# air_cylinder_control.net
KiCad netlist of a schematic drawn in Altium Designer
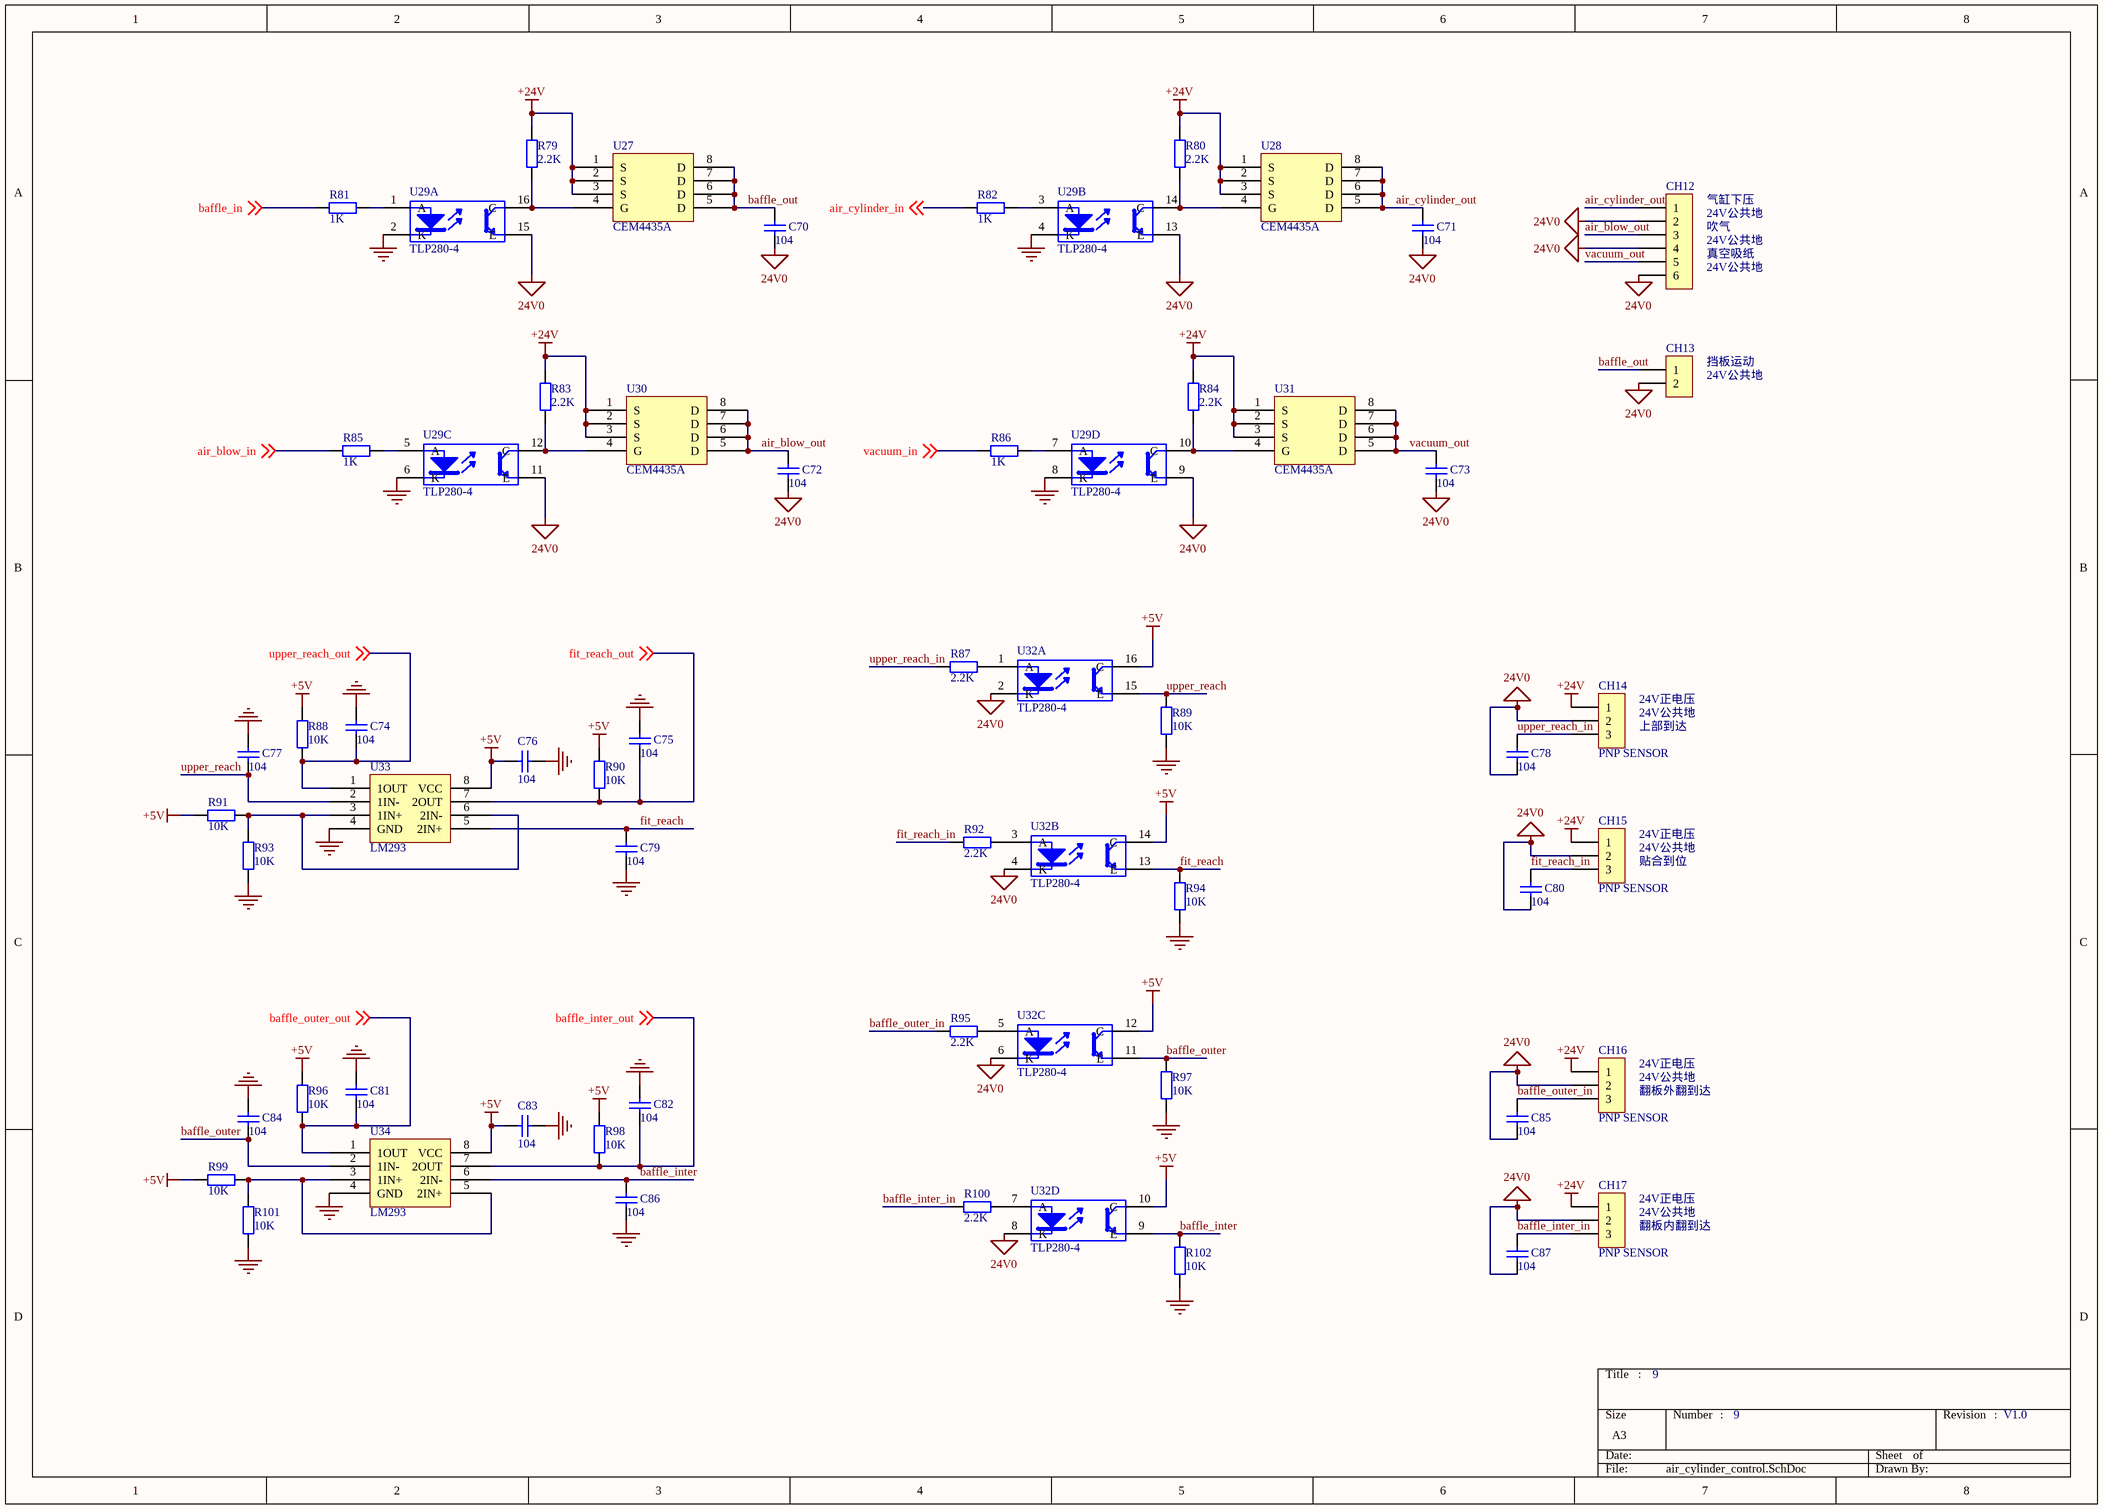
[diagram p0: air_cylinder_control.SchDoc]

(export (version "E")
  (design (tool "Eeschema 10.0.6"))
  (components
    (comp (ref "C70")
      (value "104")
      (footprint "0805")
      (description "Capacitor")
      (fields (field (name "Comment") "Cap") (field (name "PUBLISHER") "Altium Limited"))
      (libsource (lib "Miscellaneous Devices") (part "Cap"))
    )
    (comp (ref "C71")
      (value "104")
      (footprint "0805")
      (description "Capacitor")
      (fields (field (name "Comment") "Cap") (field (name "PUBLISHER") "Altium Limited"))
      (libsource (lib "Miscellaneous Devices") (part "Cap"))
    )
    (comp (ref "C72")
      (value "104")
      (footprint "0805")
      (description "Capacitor")
      (fields (field (name "Comment") "Cap") (field (name "PUBLISHER") "Altium Limited"))
      (libsource (lib "Miscellaneous Devices") (part "Cap"))
    )
    (comp (ref "C73")
      (value "104")
      (footprint "0805")
      (description "Capacitor")
      (fields (field (name "Comment") "Cap") (field (name "PUBLISHER") "Altium Limited"))
      (libsource (lib "Miscellaneous Devices") (part "Cap"))
    )
    (comp (ref "C74")
      (value "104")
      (footprint "0805")
      (description "Capacitor")
      (fields (field (name "Comment") "Cap") (field (name "PUBLISHER") "Altium Limited"))
      (libsource (lib "Miscellaneous Devices") (part "Cap"))
    )
    (comp (ref "C75")
      (value "104")
      (footprint "0805")
      (description "Capacitor")
      (fields (field (name "Comment") "Cap") (field (name "PUBLISHER") "Altium Limited"))
      (libsource (lib "Miscellaneous Devices") (part "Cap"))
    )
    (comp (ref "C76")
      (value "104")
      (footprint "0805")
      (description "Capacitor")
      (fields (field (name "Comment") "Cap") (field (name "PUBLISHER") "Altium Limited"))
      (libsource (lib "Miscellaneous Devices") (part "Cap"))
    )
    (comp (ref "C77")
      (value "104")
      (footprint "0805")
      (description "Capacitor")
      (fields (field (name "Comment") "Cap") (field (name "PUBLISHER") "Altium Limited"))
      (libsource (lib "Miscellaneous Devices") (part "Cap"))
    )
    (comp (ref "C78")
      (value "104")
      (footprint "0805")
      (description "Capacitor")
      (fields (field (name "Comment") "Cap") (field (name "PUBLISHER") "Altium Limited"))
      (libsource (lib "Miscellaneous Devices") (part "Cap"))
    )
    (comp (ref "C79")
      (value "104")
      (footprint "0805")
      (description "Capacitor")
      (fields (field (name "Comment") "Cap") (field (name "PUBLISHER") "Altium Limited"))
      (libsource (lib "Miscellaneous Devices") (part "Cap"))
    )
    (comp (ref "C80")
      (value "104")
      (footprint "0805")
      (description "Capacitor")
      (fields (field (name "Comment") "Cap") (field (name "PUBLISHER") "Altium Limited"))
      (libsource (lib "Miscellaneous Devices") (part "Cap"))
    )
    (comp (ref "C81")
      (value "104")
      (footprint "0805")
      (description "Capacitor")
      (fields (field (name "Comment") "Cap") (field (name "PUBLISHER") "Altium Limited"))
      (libsource (lib "Miscellaneous Devices") (part "Cap"))
    )
    (comp (ref "C82")
      (value "104")
      (footprint "0805")
      (description "Capacitor")
      (fields (field (name "Comment") "Cap") (field (name "PUBLISHER") "Altium Limited"))
      (libsource (lib "Miscellaneous Devices") (part "Cap"))
    )
    (comp (ref "C83")
      (value "104")
      (footprint "0805")
      (description "Capacitor")
      (fields (field (name "Comment") "Cap") (field (name "PUBLISHER") "Altium Limited"))
      (libsource (lib "Miscellaneous Devices") (part "Cap"))
    )
    (comp (ref "C84")
      (value "104")
      (footprint "0805")
      (description "Capacitor")
      (fields (field (name "Comment") "Cap") (field (name "PUBLISHER") "Altium Limited"))
      (libsource (lib "Miscellaneous Devices") (part "Cap"))
    )
    (comp (ref "C85")
      (value "104")
      (footprint "0805")
      (description "Capacitor")
      (fields (field (name "Comment") "Cap") (field (name "PUBLISHER") "Altium Limited"))
      (libsource (lib "Miscellaneous Devices") (part "Cap"))
    )
    (comp (ref "C86")
      (value "104")
      (footprint "0805")
      (description "Capacitor")
      (fields (field (name "Comment") "Cap") (field (name "PUBLISHER") "Altium Limited"))
      (libsource (lib "Miscellaneous Devices") (part "Cap"))
    )
    (comp (ref "C87")
      (value "104")
      (footprint "0805")
      (description "Capacitor")
      (fields (field (name "Comment") "Cap") (field (name "PUBLISHER") "Altium Limited"))
      (libsource (lib "Miscellaneous Devices") (part "Cap"))
    )
    (comp (ref "CH12")
      (value "HEADER1X6")
      (footprint "CH3.96-6PIN")
      (libsource (lib "myIntegrated_Library1") (part "HEADER1X6"))
    )
    (comp (ref "CH13")
      (value "HEADER1X2")
      (footprint "CH3.96-2PIN")
      (libsource (lib "myIntegrated_Library1") (part "HEADER1X2"))
    )
    (comp (ref "CH14")
      (value "HEADER1X3")
      (footprint "CH3.96-3PIN")
      (fields (field (name "ALTIUM_UNNAMED_1") "PNP SENSOR"))
      (libsource (lib "myIntegrated_Library1") (part "HEADER1X3"))
    )
    (comp (ref "CH15")
      (value "HEADER1X3")
      (footprint "CH3.96-3PIN")
      (fields (field (name "ALTIUM_UNNAMED_1") "PNP SENSOR"))
      (libsource (lib "myIntegrated_Library1") (part "HEADER1X3"))
    )
    (comp (ref "CH16")
      (value "HEADER1X3")
      (footprint "CH3.96-3PIN")
      (fields (field (name "ALTIUM_UNNAMED_1") "PNP SENSOR"))
      (libsource (lib "myIntegrated_Library1") (part "HEADER1X3"))
    )
    (comp (ref "CH17")
      (value "HEADER1X3")
      (footprint "CH3.96-3PIN")
      (fields (field (name "ALTIUM_UNNAMED_1") "PNP SENSOR"))
      (libsource (lib "myIntegrated_Library1") (part "HEADER1X3"))
    )
    (comp (ref "R79")
      (value "2.2K")
      (footprint "0805")
      (description "Resistor")
      (fields (field (name "Comment") "Res2") (field (name "PUBLISHER") "Altium Limited"))
      (libsource (lib "") (part "Res2_2"))
    )
    (comp (ref "R80")
      (value "2.2K")
      (footprint "0805")
      (description "Resistor")
      (fields (field (name "Comment") "Res2") (field (name "PUBLISHER") "Altium Limited"))
      (libsource (lib "") (part "Res2_2"))
    )
    (comp (ref "R81")
      (value "1K")
      (footprint "0805")
      (description "Resistor")
      (fields (field (name "Comment") "Res2") (field (name "PUBLISHER") "Altium Limited"))
      (libsource (lib "Miscellaneous Devices") (part "Res2"))
    )
    (comp (ref "R82")
      (value "1K")
      (footprint "0805")
      (description "Resistor")
      (fields (field (name "Comment") "Res2") (field (name "PUBLISHER") "Altium Limited"))
      (libsource (lib "Miscellaneous Devices") (part "Res2"))
    )
    (comp (ref "R83")
      (value "2.2K")
      (footprint "0805")
      (description "Resistor")
      (fields (field (name "Comment") "Res2") (field (name "PUBLISHER") "Altium Limited"))
      (libsource (lib "") (part "Res2_2"))
    )
    (comp (ref "R84")
      (value "2.2K")
      (footprint "0805")
      (description "Resistor")
      (fields (field (name "Comment") "Res2") (field (name "PUBLISHER") "Altium Limited"))
      (libsource (lib "") (part "Res2_2"))
    )
    (comp (ref "R85")
      (value "1K")
      (footprint "0805")
      (description "Resistor")
      (fields (field (name "Comment") "Res2") (field (name "PUBLISHER") "Altium Limited"))
      (libsource (lib "Miscellaneous Devices") (part "Res2"))
    )
    (comp (ref "R86")
      (value "1K")
      (footprint "0805")
      (description "Resistor")
      (fields (field (name "Comment") "Res2") (field (name "PUBLISHER") "Altium Limited"))
      (libsource (lib "Miscellaneous Devices") (part "Res2"))
    )
    (comp (ref "R87")
      (value "2.2K")
      (footprint "0805")
      (description "Resistor")
      (fields (field (name "Comment") "Res2") (field (name "PUBLISHER") "Altium Limited"))
      (libsource (lib "Miscellaneous Devices") (part "Res2"))
    )
    (comp (ref "R88")
      (value "10K")
      (footprint "0805")
      (description "Resistor")
      (fields (field (name "Comment") "Res2") (field (name "PUBLISHER") "Altium Limited"))
      (libsource (lib "") (part "Res2_1"))
    )
    (comp (ref "R89")
      (value "10K")
      (footprint "0805")
      (description "Resistor")
      (fields (field (name "Comment") "Res2") (field (name "PUBLISHER") "Altium Limited"))
      (libsource (lib "") (part "Res2_1"))
    )
    (comp (ref "R90")
      (value "10K")
      (footprint "0805")
      (description "Resistor")
      (fields (field (name "Comment") "Res2") (field (name "PUBLISHER") "Altium Limited"))
      (libsource (lib "") (part "Res2_1"))
    )
    (comp (ref "R91")
      (value "10K")
      (footprint "0805")
      (description "Resistor")
      (fields (field (name "Comment") "Res2") (field (name "PUBLISHER") "Altium Limited"))
      (libsource (lib "") (part "Res2_3"))
    )
    (comp (ref "R92")
      (value "2.2K")
      (footprint "0805")
      (description "Resistor")
      (fields (field (name "Comment") "Res2") (field (name "PUBLISHER") "Altium Limited"))
      (libsource (lib "Miscellaneous Devices") (part "Res2"))
    )
    (comp (ref "R93")
      (value "10K")
      (footprint "0805")
      (description "Resistor")
      (fields (field (name "Comment") "Res2") (field (name "PUBLISHER") "Altium Limited"))
      (libsource (lib "") (part "Res2_1"))
    )
    (comp (ref "R94")
      (value "10K")
      (footprint "0805")
      (description "Resistor")
      (fields (field (name "Comment") "Res2") (field (name "PUBLISHER") "Altium Limited"))
      (libsource (lib "") (part "Res2_1"))
    )
    (comp (ref "R95")
      (value "2.2K")
      (footprint "0805")
      (description "Resistor")
      (fields (field (name "Comment") "Res2") (field (name "PUBLISHER") "Altium Limited"))
      (libsource (lib "Miscellaneous Devices") (part "Res2"))
    )
    (comp (ref "R96")
      (value "10K")
      (footprint "0805")
      (description "Resistor")
      (fields (field (name "Comment") "Res2") (field (name "PUBLISHER") "Altium Limited"))
      (libsource (lib "") (part "Res2_1"))
    )
    (comp (ref "R97")
      (value "10K")
      (footprint "0805")
      (description "Resistor")
      (fields (field (name "Comment") "Res2") (field (name "PUBLISHER") "Altium Limited"))
      (libsource (lib "") (part "Res2_1"))
    )
    (comp (ref "R98")
      (value "10K")
      (footprint "0805")
      (description "Resistor")
      (fields (field (name "Comment") "Res2") (field (name "PUBLISHER") "Altium Limited"))
      (libsource (lib "") (part "Res2_1"))
    )
    (comp (ref "R99")
      (value "10K")
      (footprint "0805")
      (description "Resistor")
      (fields (field (name "Comment") "Res2") (field (name "PUBLISHER") "Altium Limited"))
      (libsource (lib "") (part "Res2_3"))
    )
    (comp (ref "R100")
      (value "2.2K")
      (footprint "0805")
      (description "Resistor")
      (fields (field (name "Comment") "Res2") (field (name "PUBLISHER") "Altium Limited"))
      (libsource (lib "Miscellaneous Devices") (part "Res2"))
    )
    (comp (ref "R101")
      (value "10K")
      (footprint "0805")
      (description "Resistor")
      (fields (field (name "Comment") "Res2") (field (name "PUBLISHER") "Altium Limited"))
      (libsource (lib "") (part "Res2_1"))
    )
    (comp (ref "R102")
      (value "10K")
      (footprint "0805")
      (description "Resistor")
      (fields (field (name "Comment") "Res2") (field (name "PUBLISHER") "Altium Limited"))
      (libsource (lib "") (part "Res2_1"))
    )
    (comp (ref "U27")
      (value "CEM4435A")
      (footprint "SOP8-OP27")
      (libsource (lib "myIntegrated_Library1") (part "CEM4435A"))
    )
    (comp (ref "U28")
      (value "CEM4435A")
      (footprint "SOP8-OP27")
      (libsource (lib "myIntegrated_Library1") (part "CEM4435A"))
    )
    (comp (ref "U29") (value "TLP280-4") (footprint "SO16") (libsource (lib "WH V20") (part "TLP521-4")))
    (comp (ref "U30")
      (value "CEM4435A")
      (footprint "SOP8-OP27")
      (libsource (lib "myIntegrated_Library1") (part "CEM4435A"))
    )
    (comp (ref "U31")
      (value "CEM4435A")
      (footprint "SOP8-OP27")
      (libsource (lib "myIntegrated_Library1") (part "CEM4435A"))
    )
    (comp (ref "U32") (value "TLP280-4") (footprint "SO16") (libsource (lib "WH V20") (part "TLP521-4")))
    (comp (ref "U33")
      (value "LM293")
      (footprint "SOP8-OP27")
      (libsource (lib "myIntegrated_Library1") (part "LM293"))
    )
    (comp (ref "U34")
      (value "LM293")
      (footprint "SOP8-OP27")
      (libsource (lib "myIntegrated_Library1") (part "LM293"))
    )
  )
  (nets
    (net (code "1") (name "+5V") (class "Default")
      (node (ref "C76") (pin "2") (pinfunction "2_2") (pintype "passive"))
      (node (ref "C83") (pin "2") (pinfunction "2_2") (pintype "passive"))
      (node (ref "R88") (pin "2") (pinfunction "2_2") (pintype "passive"))
      (node (ref "R90") (pin "2") (pinfunction "2_2") (pintype "passive"))
      (node (ref "R91") (pin "2") (pinfunction "2_2") (pintype "passive"))
      (node (ref "R96") (pin "2") (pinfunction "2_2") (pintype "passive"))
      (node (ref "R98") (pin "2") (pinfunction "2_2") (pintype "passive"))
      (node (ref "R99") (pin "2") (pinfunction "2_2") (pintype "passive"))
      (node (ref "U32") (pin "10") (pinfunction "C_10") (pintype "passive"))
      (node (ref "U32") (pin "12") (pinfunction "C_12") (pintype "passive"))
      (node (ref "U32") (pin "14") (pinfunction "C_14") (pintype "passive"))
      (node (ref "U32") (pin "16") (pinfunction "C_16") (pintype "passive"))
      (node (ref "U33") (pin "8") (pinfunction "VCC_8") (pintype "passive"))
      (node (ref "U34") (pin "8") (pinfunction "VCC_8") (pintype "passive"))
    )
    (net (code "2") (name "+24V") (class "Default")
      (node (ref "CH14") (pin "1") (pinfunction "1_1") (pintype "passive"))
      (node (ref "CH15") (pin "1") (pinfunction "1_1") (pintype "passive"))
      (node (ref "CH16") (pin "1") (pinfunction "1_1") (pintype "passive"))
      (node (ref "CH17") (pin "1") (pinfunction "1_1") (pintype "passive"))
      (node (ref "R79") (pin "1") (pinfunction "1_1") (pintype "passive"))
      (node (ref "R80") (pin "1") (pinfunction "1_1") (pintype "passive"))
      (node (ref "R83") (pin "1") (pinfunction "1_1") (pintype "passive"))
      (node (ref "R84") (pin "1") (pinfunction "1_1") (pintype "passive"))
      (node (ref "U27") (pin "1") (pinfunction "S_1") (pintype "passive"))
      (node (ref "U27") (pin "2") (pinfunction "S_2") (pintype "passive"))
      (node (ref "U27") (pin "3") (pinfunction "S_3") (pintype "passive"))
      (node (ref "U28") (pin "1") (pinfunction "S_1") (pintype "passive"))
      (node (ref "U28") (pin "2") (pinfunction "S_2") (pintype "passive"))
      (node (ref "U28") (pin "3") (pinfunction "S_3") (pintype "passive"))
      (node (ref "U30") (pin "1") (pinfunction "S_1") (pintype "passive"))
      (node (ref "U30") (pin "2") (pinfunction "S_2") (pintype "passive"))
      (node (ref "U30") (pin "3") (pinfunction "S_3") (pintype "passive"))
      (node (ref "U31") (pin "1") (pinfunction "S_1") (pintype "passive"))
      (node (ref "U31") (pin "2") (pinfunction "S_2") (pintype "passive"))
      (node (ref "U31") (pin "3") (pinfunction "S_3") (pintype "passive"))
    )
    (net (code "3") (name "/air_blow_out") (class "Default")
      (node (ref "C72") (pin "2") (pinfunction "2_2") (pintype "passive"))
      (node (ref "CH12") (pin "3") (pinfunction "3_3") (pintype "passive"))
      (node (ref "U30") (pin "5") (pinfunction "D_5") (pintype "passive"))
      (node (ref "U30") (pin "6") (pinfunction "D_6") (pintype "passive"))
      (node (ref "U30") (pin "7") (pinfunction "D_7") (pintype "passive"))
      (node (ref "U30") (pin "8") (pinfunction "D_8") (pintype "passive"))
    )
    (net (code "4") (name "/air_cylinder_out") (class "Default")
      (node (ref "C71") (pin "2") (pinfunction "2_2") (pintype "passive"))
      (node (ref "CH12") (pin "1") (pinfunction "1_1") (pintype "passive"))
      (node (ref "U28") (pin "5") (pinfunction "D_5") (pintype "passive"))
      (node (ref "U28") (pin "6") (pinfunction "D_6") (pintype "passive"))
      (node (ref "U28") (pin "7") (pinfunction "D_7") (pintype "passive"))
      (node (ref "U28") (pin "8") (pinfunction "D_8") (pintype "passive"))
    )
    (net (code "5") (name "/baffle_inter") (class "Default")
      (node (ref "C86") (pin "2") (pinfunction "2_2") (pintype "passive"))
      (node (ref "R102") (pin "2") (pinfunction "2_2") (pintype "passive"))
      (node (ref "U32") (pin "9") (pinfunction "E_9") (pintype "passive"))
      (node (ref "U34") (pin "6") (pinfunction "2IN-_6") (pintype "passive"))
    )
    (net (code "6") (name "/baffle_inter_in") (class "Default")
      (node (ref "C87") (pin "2") (pinfunction "2_2") (pintype "passive"))
      (node (ref "CH17") (pin "3") (pinfunction "3_3") (pintype "passive"))
      (node (ref "R100") (pin "1") (pinfunction "1_1") (pintype "passive"))
    )
    (net (code "7") (name "/baffle_out") (class "Default")
      (node (ref "C70") (pin "2") (pinfunction "2_2") (pintype "passive"))
      (node (ref "CH13") (pin "1") (pinfunction "1_1") (pintype "passive"))
      (node (ref "U27") (pin "5") (pinfunction "D_5") (pintype "passive"))
      (node (ref "U27") (pin "6") (pinfunction "D_6") (pintype "passive"))
      (node (ref "U27") (pin "7") (pinfunction "D_7") (pintype "passive"))
      (node (ref "U27") (pin "8") (pinfunction "D_8") (pintype "passive"))
    )
    (net (code "8") (name "/baffle_outer") (class "Default")
      (node (ref "C84") (pin "1") (pinfunction "1_1") (pintype "passive"))
      (node (ref "R97") (pin "2") (pinfunction "2_2") (pintype "passive"))
      (node (ref "U32") (pin "11") (pinfunction "E_11") (pintype "passive"))
      (node (ref "U34") (pin "2") (pinfunction "1IN-_2") (pintype "passive"))
    )
    (net (code "9") (name "/baffle_outer_in") (class "Default")
      (node (ref "C85") (pin "2") (pinfunction "2_2") (pintype "passive"))
      (node (ref "CH16") (pin "3") (pinfunction "3_3") (pintype "passive"))
      (node (ref "R95") (pin "1") (pinfunction "1_1") (pintype "passive"))
    )
    (net (code "10") (name "/fit_reach") (class "Default")
      (node (ref "C79") (pin "2") (pinfunction "2_2") (pintype "passive"))
      (node (ref "R94") (pin "2") (pinfunction "2_2") (pintype "passive"))
      (node (ref "U32") (pin "13") (pinfunction "E_13") (pintype "passive"))
      (node (ref "U33") (pin "5") (pinfunction "2IN+_5") (pintype "passive"))
    )
    (net (code "11") (name "/fit_reach_in") (class "Default")
      (node (ref "C80") (pin "2") (pinfunction "2_2") (pintype "passive"))
      (node (ref "CH15") (pin "3") (pinfunction "3_3") (pintype "passive"))
      (node (ref "R92") (pin "1") (pinfunction "1_1") (pintype "passive"))
    )
    (net (code "12") (name "/upper_reach") (class "Default")
      (node (ref "C77") (pin "1") (pinfunction "1_1") (pintype "passive"))
      (node (ref "R89") (pin "2") (pinfunction "2_2") (pintype "passive"))
      (node (ref "U32") (pin "15") (pinfunction "E_15") (pintype "passive"))
      (node (ref "U33") (pin "2") (pinfunction "1IN-_2") (pintype "passive"))
    )
    (net (code "13") (name "/upper_reach_in") (class "Default")
      (node (ref "C78") (pin "2") (pinfunction "2_2") (pintype "passive"))
      (node (ref "CH14") (pin "3") (pinfunction "3_3") (pintype "passive"))
      (node (ref "R87") (pin "1") (pinfunction "1_1") (pintype "passive"))
    )
    (net (code "14") (name "/vacuum_out") (class "Default")
      (node (ref "C73") (pin "2") (pinfunction "2_2") (pintype "passive"))
      (node (ref "CH12") (pin "5") (pinfunction "5_5") (pintype "passive"))
      (node (ref "U31") (pin "5") (pinfunction "D_5") (pintype "passive"))
      (node (ref "U31") (pin "6") (pinfunction "D_6") (pintype "passive"))
      (node (ref "U31") (pin "7") (pinfunction "D_7") (pintype "passive"))
      (node (ref "U31") (pin "8") (pinfunction "D_8") (pintype "passive"))
    )
    (net (code "15") (name "24V0") (class "Default")
      (node (ref "C70") (pin "1") (pinfunction "1_1") (pintype "passive"))
      (node (ref "C71") (pin "1") (pinfunction "1_1") (pintype "passive"))
      (node (ref "C72") (pin "1") (pinfunction "1_1") (pintype "passive"))
      (node (ref "C73") (pin "1") (pinfunction "1_1") (pintype "passive"))
      (node (ref "C78") (pin "1") (pinfunction "1_1") (pintype "passive"))
      (node (ref "C80") (pin "1") (pinfunction "1_1") (pintype "passive"))
      (node (ref "C85") (pin "1") (pinfunction "1_1") (pintype "passive"))
      (node (ref "C87") (pin "1") (pinfunction "1_1") (pintype "passive"))
      (node (ref "CH12") (pin "2") (pinfunction "2_2") (pintype "passive"))
      (node (ref "CH12") (pin "4") (pinfunction "4_4") (pintype "passive"))
      (node (ref "CH12") (pin "6") (pinfunction "6_6") (pintype "passive"))
      (node (ref "CH13") (pin "2") (pinfunction "2_2") (pintype "passive"))
      (node (ref "CH14") (pin "2") (pinfunction "2_2") (pintype "passive"))
      (node (ref "CH15") (pin "2") (pinfunction "2_2") (pintype "passive"))
      (node (ref "CH16") (pin "2") (pinfunction "2_2") (pintype "passive"))
      (node (ref "CH17") (pin "2") (pinfunction "2_2") (pintype "passive"))
      (node (ref "U29") (pin "11") (pinfunction "E_11") (pintype "passive"))
      (node (ref "U29") (pin "13") (pinfunction "E_13") (pintype "passive"))
      (node (ref "U29") (pin "15") (pinfunction "E_15") (pintype "passive"))
      (node (ref "U29") (pin "9") (pinfunction "E_9") (pintype "passive"))
      (node (ref "U32") (pin "2") (pinfunction "K_2") (pintype "passive"))
      (node (ref "U32") (pin "4") (pinfunction "K_4") (pintype "passive"))
      (node (ref "U32") (pin "6") (pinfunction "K_6") (pintype "passive"))
      (node (ref "U32") (pin "8") (pinfunction "K_8") (pintype "passive"))
    )
    (net (code "16") (name "GND") (class "Default")
      (node (ref "C74") (pin "2") (pinfunction "2_2") (pintype "passive"))
      (node (ref "C75") (pin "2") (pinfunction "2_2") (pintype "passive"))
      (node (ref "C76") (pin "1") (pinfunction "1_1") (pintype "passive"))
      (node (ref "C77") (pin "2") (pinfunction "2_2") (pintype "passive"))
      (node (ref "C79") (pin "1") (pinfunction "1_1") (pintype "passive"))
      (node (ref "C81") (pin "2") (pinfunction "2_2") (pintype "passive"))
      (node (ref "C82") (pin "2") (pinfunction "2_2") (pintype "passive"))
      (node (ref "C83") (pin "1") (pinfunction "1_1") (pintype "passive"))
      (node (ref "C84") (pin "2") (pinfunction "2_2") (pintype "passive"))
      (node (ref "C86") (pin "1") (pinfunction "1_1") (pintype "passive"))
      (node (ref "R101") (pin "1") (pinfunction "1_1") (pintype "passive"))
      (node (ref "R102") (pin "1") (pinfunction "1_1") (pintype "passive"))
      (node (ref "R89") (pin "1") (pinfunction "1_1") (pintype "passive"))
      (node (ref "R93") (pin "1") (pinfunction "1_1") (pintype "passive"))
      (node (ref "R94") (pin "1") (pinfunction "1_1") (pintype "passive"))
      (node (ref "R97") (pin "1") (pinfunction "1_1") (pintype "passive"))
      (node (ref "U29") (pin "2") (pinfunction "K_2") (pintype "passive"))
      (node (ref "U29") (pin "4") (pinfunction "K_4") (pintype "passive"))
      (node (ref "U29") (pin "6") (pinfunction "K_6") (pintype "passive"))
      (node (ref "U29") (pin "8") (pinfunction "K_8") (pintype "passive"))
      (node (ref "U33") (pin "4") (pinfunction "GND_4") (pintype "passive"))
      (node (ref "U34") (pin "4") (pinfunction "GND_4") (pintype "passive"))
    )
    (net (code "17") (name "Net-(U27-G)") (class "Default")
      (node (ref "R79") (pin "2") (pinfunction "2_2") (pintype "passive"))
      (node (ref "U27") (pin "4") (pinfunction "G_4") (pintype "passive"))
      (node (ref "U29") (pin "16") (pinfunction "C_16") (pintype "passive"))
    )
    (net (code "18") (name "Net-(U28-G)") (class "Default")
      (node (ref "R80") (pin "2") (pinfunction "2_2") (pintype "passive"))
      (node (ref "U28") (pin "4") (pinfunction "G_4") (pintype "passive"))
      (node (ref "U29") (pin "14") (pinfunction "C_14") (pintype "passive"))
    )
    (net (code "19") (name "Net-(U29A-A)") (class "Default")
      (node (ref "R81") (pin "2") (pinfunction "2_2") (pintype "passive"))
      (node (ref "U29") (pin "1") (pinfunction "A_1") (pintype "passive"))
    )
    (net (code "20") (name "Net-(U29B-A)") (class "Default")
      (node (ref "R82") (pin "2") (pinfunction "2_2") (pintype "passive"))
      (node (ref "U29") (pin "3") (pinfunction "A_3") (pintype "passive"))
    )
    (net (code "21") (name "Net-(U29C-A)") (class "Default")
      (node (ref "R85") (pin "2") (pinfunction "2_2") (pintype "passive"))
      (node (ref "U29") (pin "5") (pinfunction "A_5") (pintype "passive"))
    )
    (net (code "22") (name "Net-(U29C-C)") (class "Default")
      (node (ref "R83") (pin "2") (pinfunction "2_2") (pintype "passive"))
      (node (ref "U29") (pin "12") (pinfunction "C_12") (pintype "passive"))
      (node (ref "U30") (pin "4") (pinfunction "G_4") (pintype "passive"))
    )
    (net (code "23") (name "Net-(U29D-A)") (class "Default")
      (node (ref "R86") (pin "2") (pinfunction "2_2") (pintype "passive"))
      (node (ref "U29") (pin "7") (pinfunction "A_7") (pintype "passive"))
    )
    (net (code "24") (name "Net-(U29D-C)") (class "Default")
      (node (ref "R84") (pin "2") (pinfunction "2_2") (pintype "passive"))
      (node (ref "U29") (pin "10") (pinfunction "C_10") (pintype "passive"))
      (node (ref "U31") (pin "4") (pinfunction "G_4") (pintype "passive"))
    )
    (net (code "25") (name "Net-(U32A-A)") (class "Default")
      (node (ref "R87") (pin "2") (pinfunction "2_2") (pintype "passive"))
      (node (ref "U32") (pin "1") (pinfunction "A_1") (pintype "passive"))
    )
    (net (code "26") (name "Net-(U32B-A)") (class "Default")
      (node (ref "R92") (pin "2") (pinfunction "2_2") (pintype "passive"))
      (node (ref "U32") (pin "3") (pinfunction "A_3") (pintype "passive"))
    )
    (net (code "27") (name "Net-(U32C-A)") (class "Default")
      (node (ref "R95") (pin "2") (pinfunction "2_2") (pintype "passive"))
      (node (ref "U32") (pin "5") (pinfunction "A_5") (pintype "passive"))
    )
    (net (code "28") (name "Net-(U32D-A)") (class "Default")
      (node (ref "R100") (pin "2") (pinfunction "2_2") (pintype "passive"))
      (node (ref "U32") (pin "7") (pinfunction "A_7") (pintype "passive"))
    )
    (net (code "29") (name "Net-(U33-1IN+)") (class "Default")
      (node (ref "R91") (pin "1") (pinfunction "1_1") (pintype "passive"))
      (node (ref "R93") (pin "2") (pinfunction "2_2") (pintype "passive"))
      (node (ref "U33") (pin "3") (pinfunction "1IN+_3") (pintype "passive"))
      (node (ref "U33") (pin "6") (pinfunction "2IN-_6") (pintype "passive"))
    )
    (net (code "30") (name "Net-(U34-1IN+)") (class "Default")
      (node (ref "R101") (pin "2") (pinfunction "2_2") (pintype "passive"))
      (node (ref "R99") (pin "1") (pinfunction "1_1") (pintype "passive"))
      (node (ref "U34") (pin "3") (pinfunction "1IN+_3") (pintype "passive"))
      (node (ref "U34") (pin "5") (pinfunction "2IN+_5") (pintype "passive"))
    )
    (net (code "31") (name "air_blow_in") (class "Default")
      (node (ref "R85") (pin "1") (pinfunction "1_1") (pintype "passive"))
    )
    (net (code "32") (name "air_cylinder_in") (class "Default")
      (node (ref "R82") (pin "1") (pinfunction "1_1") (pintype "passive"))
    )
    (net (code "33") (name "baffle_in") (class "Default")
      (node (ref "R81") (pin "1") (pinfunction "1_1") (pintype "passive"))
    )
    (net (code "34") (name "baffle_inter_out") (class "Default")
      (node (ref "C82") (pin "1") (pinfunction "1_1") (pintype "passive"))
      (node (ref "R98") (pin "1") (pinfunction "1_1") (pintype "passive"))
      (node (ref "U34") (pin "7") (pinfunction "2OUT_7") (pintype "passive"))
    )
    (net (code "35") (name "baffle_outer_out") (class "Default")
      (node (ref "C81") (pin "1") (pinfunction "1_1") (pintype "passive"))
      (node (ref "R96") (pin "1") (pinfunction "1_1") (pintype "passive"))
      (node (ref "U34") (pin "1") (pinfunction "1OUT_1") (pintype "passive"))
    )
    (net (code "36") (name "fit_reach_out") (class "Default")
      (node (ref "C75") (pin "1") (pinfunction "1_1") (pintype "passive"))
      (node (ref "R90") (pin "1") (pinfunction "1_1") (pintype "passive"))
      (node (ref "U33") (pin "7") (pinfunction "2OUT_7") (pintype "passive"))
    )
    (net (code "37") (name "upper_reach_out") (class "Default")
      (node (ref "C74") (pin "1") (pinfunction "1_1") (pintype "passive"))
      (node (ref "R88") (pin "1") (pinfunction "1_1") (pintype "passive"))
      (node (ref "U33") (pin "1") (pinfunction "1OUT_1") (pintype "passive"))
    )
    (net (code "38") (name "vacuum_in") (class "Default")
      (node (ref "R86") (pin "1") (pinfunction "1_1") (pintype "passive"))
    )
  )
)
